# Radio_WMCU.net
KiCad netlist of a schematic drawn in Altium Designer
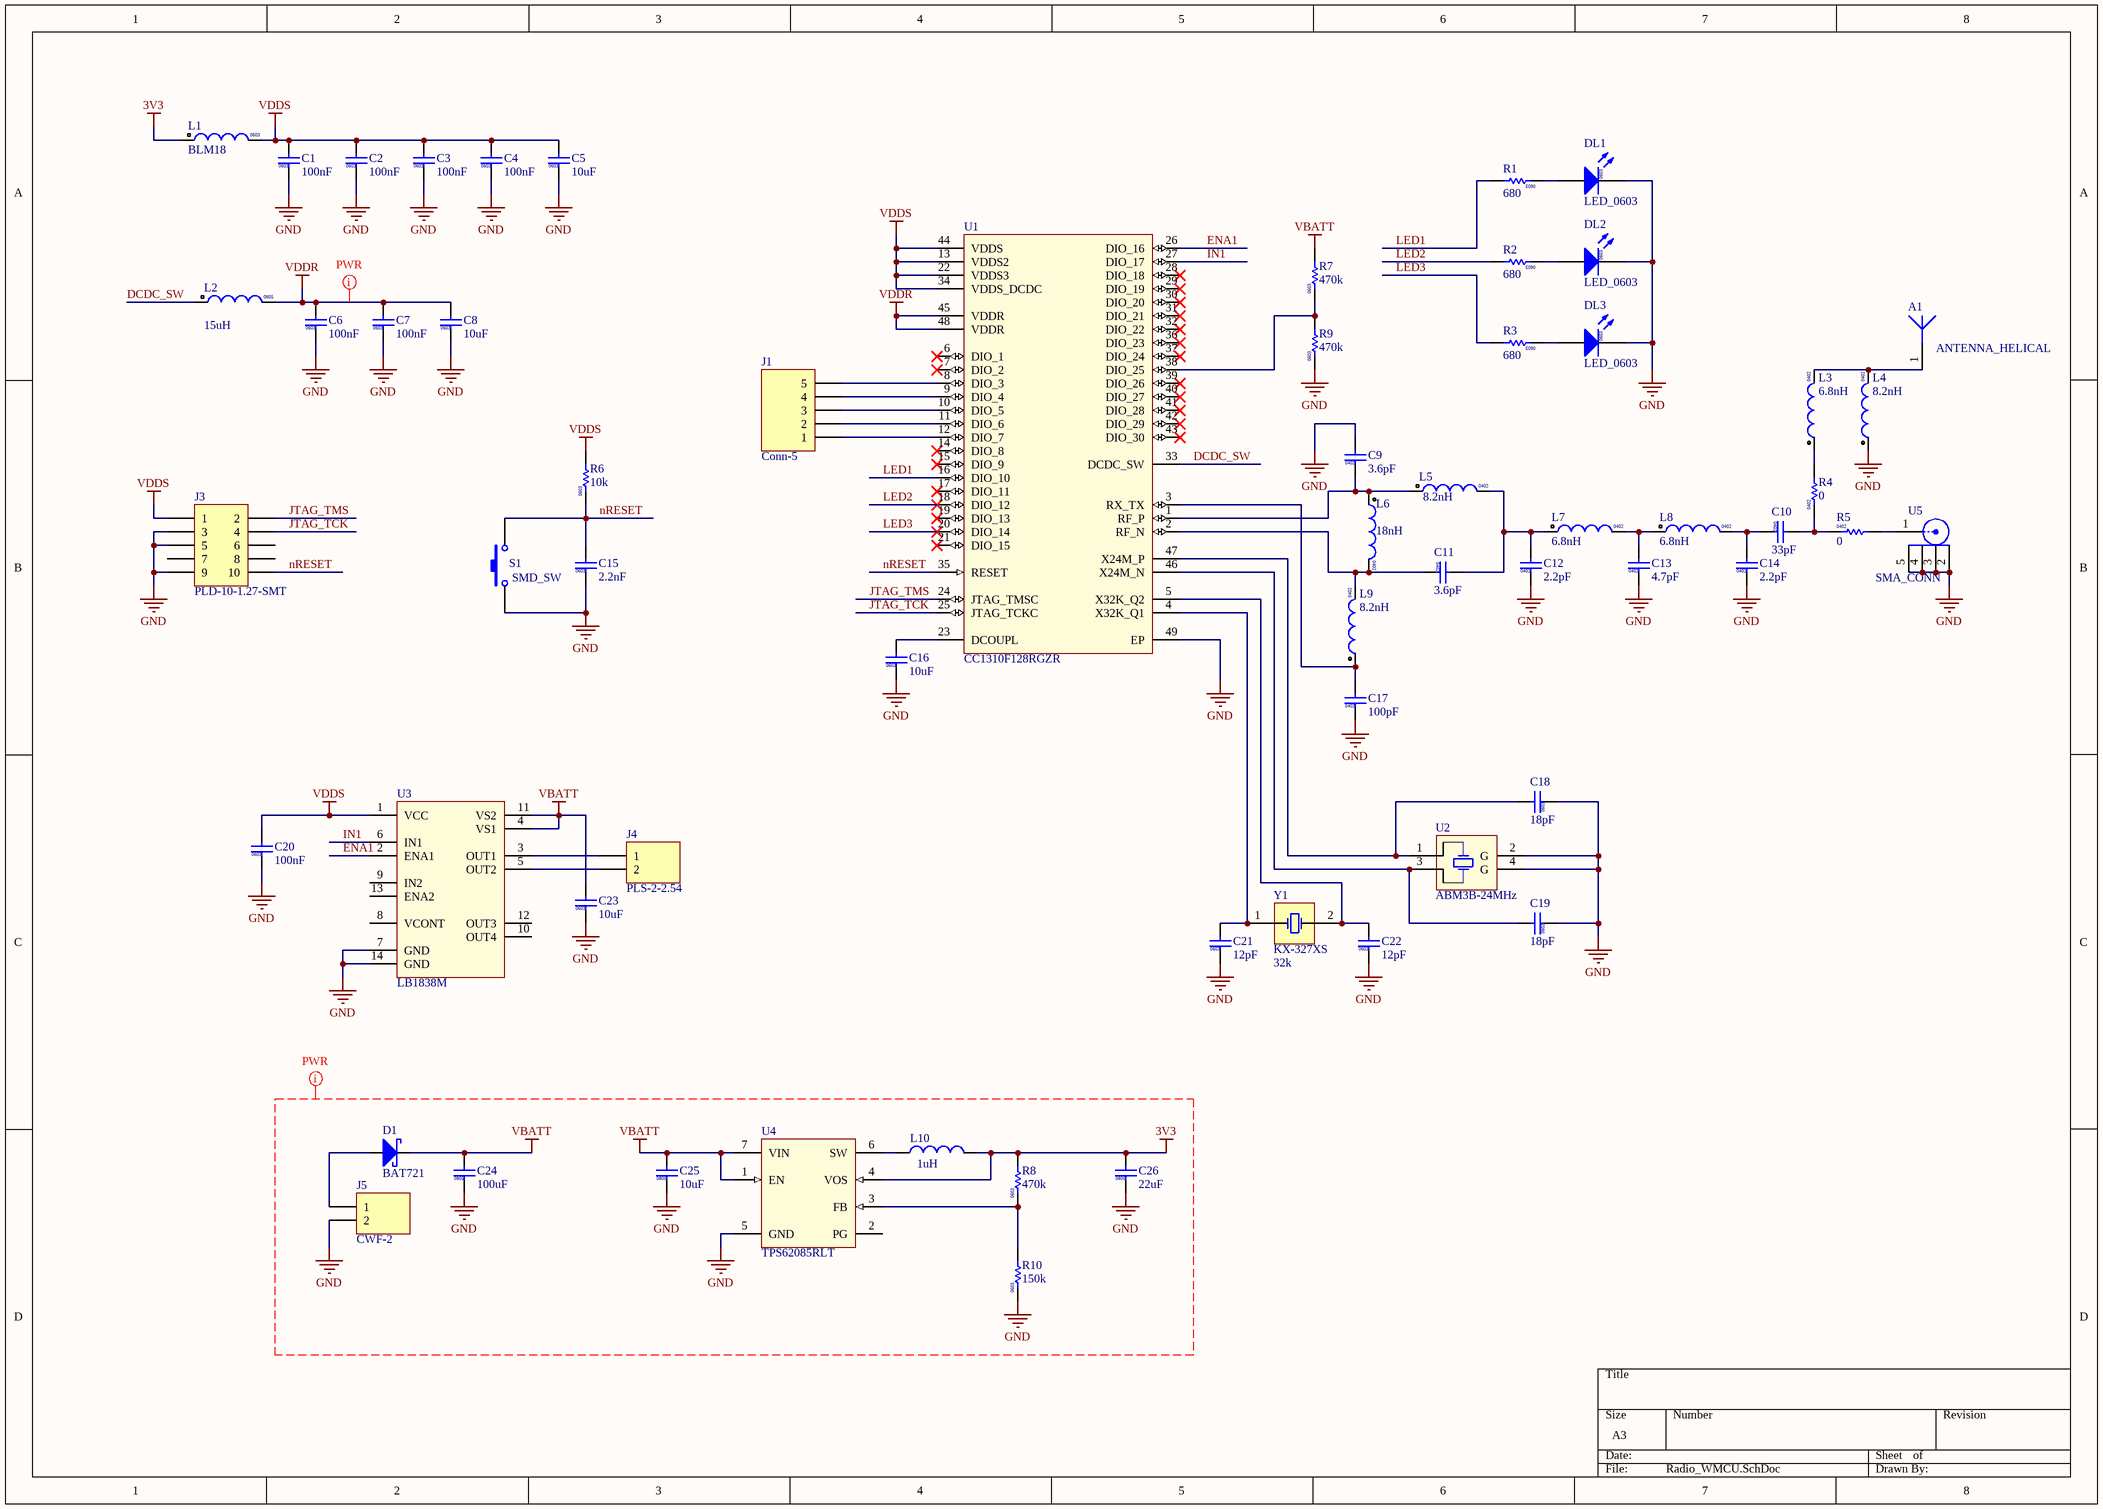
[diagram p0: Radio_WMCU.SchDoc]

(export (version "E")
  (design (tool "Eeschema 10.0.6"))
  (components
    (comp (ref "A1")
      (value "ANTENNA_HELICAL")
      (footprint "ANTENNA")
      (description "PCB helical antenna")
      (libsource (lib "Discrete") (part "ANTENNA_HELICAL"))
    )
    (comp (ref "C1")
      (value "100nF")
      (footprint "CAPC1608-0603M")
      (description "Capacitor 0603")
      (fields (field (name "Comment") "CAPC_0603"))
      (libsource (lib "Passive") (part "CAPC_0603"))
    )
    (comp (ref "C2")
      (value "100nF")
      (footprint "CAPC1608-0603M")
      (description "Capacitor 0603")
      (fields (field (name "Comment") "CAPC_0603"))
      (libsource (lib "Passive") (part "CAPC_0603"))
    )
    (comp (ref "C3")
      (value "100nF")
      (footprint "CAPC1608-0603M")
      (description "Capacitor 0603")
      (fields (field (name "Comment") "CAPC_0603"))
      (libsource (lib "Passive") (part "CAPC_0603"))
    )
    (comp (ref "C4")
      (value "100nF")
      (footprint "CAPC1608-0603M")
      (description "Capacitor 0603")
      (fields (field (name "Comment") "CAPC_0603"))
      (libsource (lib "Passive") (part "CAPC_0603"))
    )
    (comp (ref "C5")
      (value "10uF")
      (footprint "CAPC1608-0603M")
      (description "Capacitor 0603")
      (fields (field (name "Comment") "CAPC_0603"))
      (libsource (lib "Passive") (part "CAPC_0603"))
    )
    (comp (ref "C6")
      (value "100nF")
      (footprint "CAPC1608-0603M")
      (description "Capacitor 0603")
      (fields (field (name "Comment") "CAPC_0603"))
      (libsource (lib "Passive") (part "CAPC_0603"))
    )
    (comp (ref "C7")
      (value "100nF")
      (footprint "CAPC1608-0603M")
      (description "Capacitor 0603")
      (fields (field (name "Comment") "CAPC_0603"))
      (libsource (lib "Passive") (part "CAPC_0603"))
    )
    (comp (ref "C8")
      (value "10uF")
      (footprint "CAPC1608-0603M")
      (description "Capacitor 0603")
      (fields (field (name "Comment") "CAPC_0603"))
      (libsource (lib "Passive") (part "CAPC_0603"))
    )
    (comp (ref "C9")
      (value "3.6pF")
      (footprint "CAPC1005-0402M")
      (description "Capacitor 0402")
      (fields (field (name "Comment") "CAPC_0402"))
      (libsource (lib "Passive") (part "CAPC_0402"))
    )
    (comp (ref "C10")
      (value "33pF")
      (footprint "CAPC1005-0402M")
      (description "Capacitor 0402")
      (fields (field (name "Comment") "CAPC_0402"))
      (libsource (lib "Passive") (part "CAPC_0402"))
    )
    (comp (ref "C11")
      (value "3.6pF")
      (footprint "CAPC1005-0402M")
      (description "Capacitor 0402")
      (fields (field (name "Comment") "CAPC_0402"))
      (libsource (lib "Passive") (part "CAPC_0402"))
    )
    (comp (ref "C12")
      (value "2.2pF")
      (footprint "CAPC1005-0402M")
      (description "Capacitor 0402")
      (fields (field (name "Comment") "CAPC_0402"))
      (libsource (lib "Passive") (part "CAPC_0402"))
    )
    (comp (ref "C13")
      (value "4.7pF")
      (footprint "CAPC1005-0402M")
      (description "Capacitor 0402")
      (fields (field (name "Comment") "CAPC_0402"))
      (libsource (lib "Passive") (part "CAPC_0402"))
    )
    (comp (ref "C14")
      (value "2.2pF")
      (footprint "CAPC1005-0402M")
      (description "Capacitor 0402")
      (fields (field (name "Comment") "CAPC_0402"))
      (libsource (lib "Passive") (part "CAPC_0402"))
    )
    (comp (ref "C15")
      (value "2.2nF")
      (footprint "CAPC1608-0603M")
      (description "Capacitor 0603")
      (fields (field (name "Comment") "CAPC_0603"))
      (libsource (lib "Passive") (part "CAPC_0603"))
    )
    (comp (ref "C16")
      (value "10uF")
      (footprint "CAPC1608-0603M")
      (description "Capacitor 0603")
      (fields (field (name "Comment") "CAPC_0603"))
      (libsource (lib "Passive") (part "CAPC_0603"))
    )
    (comp (ref "C17")
      (value "100pF")
      (footprint "CAPC1005-0402M")
      (description "Capacitor 0402")
      (fields (field (name "Comment") "CAPC_0402"))
      (libsource (lib "Passive") (part "CAPC_0402"))
    )
    (comp (ref "C18")
      (value "18pF")
      (footprint "CAPC1608-0603M")
      (description "Capacitor 0603")
      (fields (field (name "Comment") "CAPC_0603"))
      (libsource (lib "Passive") (part "CAPC_0603"))
    )
    (comp (ref "C19")
      (value "18pF")
      (footprint "CAPC1608-0603M")
      (description "Capacitor 0603")
      (fields (field (name "Comment") "CAPC_0603"))
      (libsource (lib "Passive") (part "CAPC_0603"))
    )
    (comp (ref "C20")
      (value "100nF")
      (footprint "CAPC1608-0603M")
      (description "Capacitor 0603")
      (fields (field (name "Comment") "CAPC_0603"))
      (libsource (lib "Passive") (part "CAPC_0603"))
    )
    (comp (ref "C21")
      (value "12pF")
      (footprint "CAPC1608-0603M")
      (description "Capacitor 0603")
      (fields (field (name "Comment") "CAPC_0603"))
      (libsource (lib "Passive") (part "CAPC_0603"))
    )
    (comp (ref "C22")
      (value "12pF")
      (footprint "CAPC1608-0603M")
      (description "Capacitor 0603")
      (fields (field (name "Comment") "CAPC_0603"))
      (libsource (lib "Passive") (part "CAPC_0603"))
    )
    (comp (ref "C23")
      (value "10uF")
      (footprint "CAPC1608-0603M")
      (description "Capacitor 0603")
      (fields (field (name "Comment") "CAPC_0603"))
      (libsource (lib "Passive") (part "CAPC_0603"))
    )
    (comp (ref "C24")
      (value "100uF")
      (footprint "CAPC2012-0805M")
      (description "Capacitor 0805")
      (fields (field (name "Comment") "CAPC_0805"))
      (libsource (lib "Passive") (part "CAPC_0805"))
    )
    (comp (ref "C25")
      (value "10uF")
      (footprint "CAPC2012-0805M")
      (description "Capacitor 0805")
      (fields (field (name "Comment") "CAPC_0805"))
      (libsource (lib "Passive") (part "CAPC_0805"))
    )
    (comp (ref "C26")
      (value "22uF")
      (footprint "CAPC2012-0805M")
      (description "Capacitor 0805")
      (fields (field (name "Comment") "CAPC_0805"))
      (libsource (lib "Passive") (part "CAPC_0805"))
    )
    (comp (ref "D1")
      (value "BAT721")
      (footprint "SOT23-3M")
      (description "BAT721 Schottky diode(s)")
      (libsource (lib "Discrete") (part "BAT721"))
    )
    (comp (ref "DL1")
      (value "LED_0603")
      (footprint "DIODEC1608-0603")
      (description "LED 0603")
      (fields (field (name "PART NUMBER") "*BL-..."))
      (libsource (lib "Discrete") (part "LED_0603"))
    )
    (comp (ref "DL2")
      (value "LED_0603")
      (footprint "DIODEC1608-0603")
      (description "LED 0603")
      (fields (field (name "PART NUMBER") "*BL-..."))
      (libsource (lib "Discrete") (part "LED_0603"))
    )
    (comp (ref "DL3")
      (value "LED_0603")
      (footprint "DIODEC1608-0603")
      (description "LED 0603")
      (fields (field (name "PART NUMBER") "*BL-..."))
      (libsource (lib "Discrete") (part "LED_0603"))
    )
    (comp (ref "J1")
      (value "Conn-5")
      (footprint "CONN-5-2.54")
      (description "Header, 6-Pin, Dual row")
      (fields (field (name "PUBLISHER") "Altium Limited"))
      (libsource (lib "Connectors_dif") (part "Conn-5"))
    )
    (comp (ref "J3")
      (value "PLD-10-1.27-SMT")
      (footprint "PLD-10-1.27-SMT")
      (fields (field (name "PUBLISHER") "Altium Limited"))
      (libsource (lib "Connectors_dif") (part "PLD-10-1.27-SMT"))
    )
    (comp (ref "J4")
      (value "PLS-2-2.54")
      (footprint "PLS-2-2.54")
      (fields (field (name "PUBLISHER") "Altium Limited"))
      (libsource (lib "Connectors_dif") (part "PLS-2-2.54"))
    )
    (comp (ref "J5") (value "CWF-2") (footprint "CWF-2") (libsource (lib "Connectors_dif") (part "CWF-2")))
    (comp (ref "L1")
      (value "BLM18")
      (footprint "INDC1608M")
      (description "Chip Inductor, Body Body 1.6x0.8mm")
      (fields (field (name "Comment") "INDC-0603"))
      (libsource (lib "Passive") (part "INDC-0603"))
    )
    (comp (ref "L2")
      (value "15uH")
      (footprint "INDC2012M")
      (description "Chip Inductor, Body Body 2.0x1.2mm")
      (fields (field (name "Comment") "INDC-0805"))
      (libsource (lib "Passive") (part "INDC-0805"))
    )
    (comp (ref "L3")
      (value "6.8nH")
      (footprint "INDC1005-0402-RF2.4GHz")
      (description "Chip Inductor, Body 1.0x0.5mm")
      (fields (field (name "Comment") "INDC-0402") (field (name "PUBLISHER") "Altium Limited"))
      (libsource (lib "Passive") (part "INDC-0402"))
    )
    (comp (ref "L4")
      (value "8.2nH")
      (footprint "INDC1005-0402-RF2.4GHz")
      (description "Chip Inductor, Body 1.0x0.5mm")
      (fields (field (name "Comment") "INDC-0402") (field (name "PUBLISHER") "Altium Limited"))
      (libsource (lib "Passive") (part "INDC-0402"))
    )
    (comp (ref "L5")
      (value "8.2nH")
      (footprint "INDC1005-0402-RF2.4GHz")
      (description "Chip Inductor, Body 1.0x0.5mm")
      (fields (field (name "Comment") "INDC-0402") (field (name "PUBLISHER") "Altium Limited"))
      (libsource (lib "") (part "INDC-0402_1"))
    )
    (comp (ref "L6")
      (value "18nH")
      (footprint "INDC1005-0402-RF2.4GHz")
      (description "Chip Inductor, Body 1.0x0.5mm")
      (fields (field (name "Comment") "INDC-0402") (field (name "PUBLISHER") "Altium Limited"))
      (libsource (lib "Passive") (part "INDC-0402"))
    )
    (comp (ref "L7")
      (value "6.8nH")
      (footprint "INDC1005-0402-RF2.4GHz")
      (description "Chip Inductor, Body 1.0x0.5mm")
      (fields (field (name "Comment") "INDC-0402") (field (name "PUBLISHER") "Altium Limited"))
      (libsource (lib "Passive") (part "INDC-0402"))
    )
    (comp (ref "L8")
      (value "6.8nH")
      (footprint "INDC1005-0402-RF2.4GHz")
      (description "Chip Inductor, Body 1.0x0.5mm")
      (fields (field (name "Comment") "INDC-0402") (field (name "PUBLISHER") "Altium Limited"))
      (libsource (lib "Passive") (part "INDC-0402"))
    )
    (comp (ref "L9")
      (value "8.2nH")
      (footprint "INDC1005-0402-RF2.4GHz")
      (description "Chip Inductor, Body 1.0x0.5mm")
      (fields (field (name "Comment") "INDC-0402") (field (name "PUBLISHER") "Altium Limited"))
      (libsource (lib "Passive") (part "INDC-0402"))
    )
    (comp (ref "L10")
      (value "1uH")
      (footprint "XFL4015")
      (description "Power Inductors")
      (fields (field (name "Comment") "XFL4015"))
      (libsource (lib "Passive") (part "XFL4015"))
    )
    (comp (ref "R1")
      (value "680")
      (footprint "RESC1608-0603M")
      (description "Resistor 0603")
      (fields (field (name "Comment") "RESC_0603"))
      (libsource (lib "Passive") (part "RESC_0603"))
    )
    (comp (ref "R2")
      (value "680")
      (footprint "RESC1608-0603M")
      (description "Resistor 0603")
      (fields (field (name "Comment") "RESC_0603"))
      (libsource (lib "Passive") (part "RESC_0603"))
    )
    (comp (ref "R3")
      (value "680")
      (footprint "RESC1608-0603M")
      (description "Resistor 0603")
      (fields (field (name "Comment") "RESC_0603"))
      (libsource (lib "Passive") (part "RESC_0603"))
    )
    (comp (ref "R4")
      (value "0")
      (footprint "RESC1005-0402M")
      (description "Resistor 0402")
      (fields (field (name "Comment") "RESC_0402"))
      (libsource (lib "Passive") (part "RESC_0402"))
    )
    (comp (ref "R5")
      (value "0")
      (footprint "RESC1005-0402M")
      (description "Resistor 0402")
      (fields (field (name "Comment") "RESC_0402"))
      (libsource (lib "Passive") (part "RESC_0402"))
    )
    (comp (ref "R6")
      (value "10k")
      (footprint "RESC1608-0603M")
      (description "Resistor 0603")
      (fields (field (name "Comment") "RESC_0603"))
      (libsource (lib "Passive") (part "RESC_0603"))
    )
    (comp (ref "R7")
      (value "470k")
      (footprint "RESC1608-0603M")
      (description "Resistor 0603")
      (fields (field (name "Comment") "RESC_0603"))
      (libsource (lib "Passive") (part "RESC_0603"))
    )
    (comp (ref "R8")
      (value "470k")
      (footprint "RESC1608-0603M")
      (description "Resistor 0603")
      (fields (field (name "Comment") "RESC_0603"))
      (libsource (lib "Passive") (part "RESC_0603"))
    )
    (comp (ref "R9")
      (value "470k")
      (footprint "RESC1608-0603M")
      (description "Resistor 0603")
      (fields (field (name "Comment") "RESC_0603"))
      (libsource (lib "Passive") (part "RESC_0603"))
    )
    (comp (ref "R10")
      (value "150k")
      (footprint "RESC1608-0603M")
      (description "Resistor 0603")
      (fields (field (name "Comment") "RESC_0603"))
      (libsource (lib "Passive") (part "RESC_0603"))
    )
    (comp (ref "S1")
      (value "SMD_SW")
      (footprint "SMD_SW_1")
      (description "Switch")
      (fields (field (name "PUBLISHER") "Altium Limited"))
      (libsource (lib "General_Proj") (part "SMD_SW"))
    )
    (comp (ref "U1")
      (value "CC1310F128RGZR")
      (footprint "QFN-48M")
      (description "Ultralow Power Sub-1-GHz Wireless MCU")
      (libsource (lib "Analog_IC") (part "CC1310F128RGZR"))
    )
    (comp (ref "U2")
      (value "ABM3B-24MHz")
      (footprint "ABM3B-24MHz")
      (description "Crystal Oscillator, 24 MHz, SMD, 5mm x 3.2mm")
      (libsource (lib "Passive") (part "ABM3B-24MHz"))
    )
    (comp (ref "U3")
      (value "LB1838M")
      (footprint "MFP14S_M")
      (description "Low-Voltage, Bidiractional Motor Driver")
      (libsource (lib "Analog_IC") (part "LB1838M"))
    )
    (comp (ref "U4")
      (value "TPS62085RLT")
      (footprint "RLT7-0506")
      (description "Step-Down Converter With Hiccup Short-Circuit Protection, 2.5-V to 6.0-V input Voltage Range")
      (libsource (lib "Analog_IC") (part "TPS62085RLT"))
    )
    (comp (ref "U5")
      (value "SMA_CONN")
      (footprint "SMA_CONN")
      (description "SMA Straight PCB Socket")
      (libsource (lib "RCMG") (part "SMA_CONN"))
    )
    (comp (ref "Y1")
      (value "KX-327XS")
      (footprint "KX-327xs")
      (description "Surface Mount Quartz Crystal")
      (fields (field (name "ALTIUM_VALUE") "32k"))
      (libsource (lib "Passive") (part "KX-327XS"))
    )
  )
  (nets
    (net (code "1") (name "/DCDC_SW") (class "Default")
      (node (ref "L2") (pin "1") (pinfunction "1_1") (pintype "passive"))
      (node (ref "U1") (pin "33") (pinfunction "DCDC_SW_33") (pintype "power_in"))
    )
    (net (code "2") (name "/ENA1") (class "Default")
      (node (ref "U1") (pin "26") (pinfunction "DIO_16_26") (pintype "bidirectional"))
      (node (ref "U3") (pin "2") (pinfunction "ENA1_2") (pintype "passive"))
    )
    (net (code "3") (name "/IN1") (class "Default")
      (node (ref "U1") (pin "27") (pinfunction "DIO_17_27") (pintype "bidirectional"))
      (node (ref "U3") (pin "6") (pinfunction "IN1_6") (pintype "passive"))
    )
    (net (code "4") (name "/JTAG_TCK") (class "Default")
      (node (ref "J3") (pin "4") (pinfunction "4_4") (pintype "passive"))
      (node (ref "U1") (pin "25") (pinfunction "JTAG_TCKC_25") (pintype "bidirectional"))
    )
    (net (code "5") (name "/JTAG_TMS") (class "Default")
      (node (ref "J3") (pin "2") (pinfunction "2_2") (pintype "passive"))
      (node (ref "U1") (pin "24") (pinfunction "JTAG_TMSC_24") (pintype "bidirectional"))
    )
    (net (code "6") (name "/LED1") (class "Default")
      (node (ref "R1") (pin "2") (pinfunction "2_2") (pintype "passive"))
      (node (ref "U1") (pin "16") (pinfunction "DIO_10_16") (pintype "bidirectional"))
    )
    (net (code "7") (name "/LED2") (class "Default")
      (node (ref "R2") (pin "2") (pinfunction "2_2") (pintype "passive"))
      (node (ref "U1") (pin "18") (pinfunction "DIO_12_18") (pintype "bidirectional"))
    )
    (net (code "8") (name "/LED3") (class "Default")
      (node (ref "R3") (pin "2") (pinfunction "2_2") (pintype "passive"))
      (node (ref "U1") (pin "20") (pinfunction "DIO_14_20") (pintype "bidirectional"))
    )
    (net (code "9") (name "/nRESET") (class "Default")
      (node (ref "C15") (pin "2") (pinfunction "2_2") (pintype "passive"))
      (node (ref "J3") (pin "10") (pinfunction "10_10") (pintype "passive"))
      (node (ref "R6") (pin "1") (pinfunction "1_1") (pintype "passive"))
      (node (ref "S1") (pin "2") (pinfunction "2_2") (pintype "passive"))
      (node (ref "U1") (pin "35") (pinfunction "RESET_35") (pintype "input"))
    )
    (net (code "10") (name "3V3") (class "Default")
      (node (ref "C26") (pin "2") (pinfunction "2_2") (pintype "passive"))
      (node (ref "L1") (pin "1") (pinfunction "1_1") (pintype "passive"))
      (node (ref "L10") (pin "2") (pinfunction "2_2") (pintype "passive"))
      (node (ref "R8") (pin "2") (pinfunction "2_2") (pintype "passive"))
      (node (ref "U4") (pin "4") (pinfunction "VOS_4") (pintype "input"))
    )
    (net (code "11") (name "GND") (class "Default")
      (node (ref "C1") (pin "1") (pinfunction "1_1") (pintype "passive"))
      (node (ref "C12") (pin "1") (pinfunction "1_1") (pintype "passive"))
      (node (ref "C13") (pin "1") (pinfunction "1_1") (pintype "passive"))
      (node (ref "C14") (pin "1") (pinfunction "1_1") (pintype "passive"))
      (node (ref "C15") (pin "1") (pinfunction "1_1") (pintype "passive"))
      (node (ref "C16") (pin "1") (pinfunction "1_1") (pintype "passive"))
      (node (ref "C17") (pin "1") (pinfunction "1_1") (pintype "passive"))
      (node (ref "C18") (pin "1") (pinfunction "1_1") (pintype "passive"))
      (node (ref "C19") (pin "1") (pinfunction "1_1") (pintype "passive"))
      (node (ref "C2") (pin "1") (pinfunction "1_1") (pintype "passive"))
      (node (ref "C20") (pin "1") (pinfunction "1_1") (pintype "passive"))
      (node (ref "C21") (pin "1") (pinfunction "1_1") (pintype "passive"))
      (node (ref "C22") (pin "1") (pinfunction "1_1") (pintype "passive"))
      (node (ref "C23") (pin "1") (pinfunction "1_1") (pintype "passive"))
      (node (ref "C24") (pin "1") (pinfunction "1_1") (pintype "passive"))
      (node (ref "C25") (pin "1") (pinfunction "1_1") (pintype "passive"))
      (node (ref "C26") (pin "1") (pinfunction "1_1") (pintype "passive"))
      (node (ref "C3") (pin "1") (pinfunction "1_1") (pintype "passive"))
      (node (ref "C4") (pin "1") (pinfunction "1_1") (pintype "passive"))
      (node (ref "C5") (pin "1") (pinfunction "1_1") (pintype "passive"))
      (node (ref "C6") (pin "1") (pinfunction "1_1") (pintype "passive"))
      (node (ref "C7") (pin "1") (pinfunction "1_1") (pintype "passive"))
      (node (ref "C8") (pin "1") (pinfunction "1_1") (pintype "passive"))
      (node (ref "C9") (pin "2") (pinfunction "2_2") (pintype "passive"))
      (node (ref "DL1") (pin "2") (pinfunction "K_2") (pintype "passive"))
      (node (ref "DL2") (pin "2") (pinfunction "K_2") (pintype "passive"))
      (node (ref "DL3") (pin "2") (pinfunction "K_2") (pintype "passive"))
      (node (ref "J3") (pin "3") (pinfunction "3_3") (pintype "passive"))
      (node (ref "J3") (pin "5") (pinfunction "5_5") (pintype "passive"))
      (node (ref "J3") (pin "9") (pinfunction "9_9") (pintype "passive"))
      (node (ref "J5") (pin "2") (pinfunction "2_2") (pintype "passive"))
      (node (ref "L4") (pin "1") (pinfunction "1_1") (pintype "passive"))
      (node (ref "R10") (pin "1") (pinfunction "1_1") (pintype "passive"))
      (node (ref "R9") (pin "1") (pinfunction "1_1") (pintype "passive"))
      (node (ref "S1") (pin "1") (pinfunction "1_1") (pintype "passive"))
      (node (ref "U1") (pin "49") (pinfunction "EP_49") (pintype "power_in"))
      (node (ref "U2") (pin "2") (pinfunction "G_2") (pintype "power_in"))
      (node (ref "U2") (pin "4") (pinfunction "G_4") (pintype "power_in"))
      (node (ref "U3") (pin "14") (pinfunction "GND_14") (pintype "power_in"))
      (node (ref "U3") (pin "7") (pinfunction "GND_7") (pintype "power_in"))
      (node (ref "U4") (pin "5") (pinfunction "GND_5") (pintype "power_in"))
      (node (ref "U5") (pin "2") (pinfunction "2_2") (pintype "passive"))
      (node (ref "U5") (pin "3") (pinfunction "3_3") (pintype "passive"))
      (node (ref "U5") (pin "4") (pinfunction "4_4") (pintype "passive"))
      (node (ref "U5") (pin "5") (pinfunction "5_5") (pintype "passive"))
    )
    (net (code "12") (name "Net-(A1-Pad1)") (class "Default")
      (node (ref "A1") (pin "1") (pinfunction "1_1") (pintype "passive"))
      (node (ref "L3") (pin "2") (pinfunction "2_2") (pintype "passive"))
      (node (ref "L4") (pin "2") (pinfunction "2_2") (pintype "passive"))
    )
    (net (code "13") (name "Net-(C10-Pad1)") (class "Default")
      (node (ref "C10") (pin "1") (pinfunction "1_1") (pintype "passive"))
      (node (ref "C14") (pin "2") (pinfunction "2_2") (pintype "passive"))
      (node (ref "L8") (pin "2") (pinfunction "2_2") (pintype "passive"))
    )
    (net (code "14") (name "Net-(C10-Pad2)") (class "Default")
      (node (ref "C10") (pin "2") (pinfunction "2_2") (pintype "passive"))
      (node (ref "R4") (pin "1") (pinfunction "1_1") (pintype "passive"))
      (node (ref "R5") (pin "1") (pinfunction "1_1") (pintype "passive"))
    )
    (net (code "15") (name "Net-(C11-Pad2)") (class "Default")
      (node (ref "C11") (pin "2") (pinfunction "2_2") (pintype "passive"))
      (node (ref "C12") (pin "2") (pinfunction "2_2") (pintype "passive"))
      (node (ref "L5") (pin "2") (pinfunction "2_2") (pintype "passive"))
      (node (ref "L7") (pin "1") (pinfunction "1_1") (pintype "passive"))
    )
    (net (code "16") (name "Net-(C13-Pad2)") (class "Default")
      (node (ref "C13") (pin "2") (pinfunction "2_2") (pintype "passive"))
      (node (ref "L7") (pin "2") (pinfunction "2_2") (pintype "passive"))
      (node (ref "L8") (pin "1") (pinfunction "1_1") (pintype "passive"))
    )
    (net (code "17") (name "Net-(D1-A)") (class "Default")
      (node (ref "D1") (pin "1") (pinfunction "A_1") (pintype "passive"))
      (node (ref "J5") (pin "1") (pinfunction "1_1") (pintype "passive"))
    )
    (net (code "18") (name "Net-(DL1-A)") (class "Default")
      (node (ref "DL1") (pin "1") (pinfunction "A_1") (pintype "passive"))
      (node (ref "R1") (pin "1") (pinfunction "1_1") (pintype "passive"))
    )
    (net (code "19") (name "Net-(DL2-A)") (class "Default")
      (node (ref "DL2") (pin "1") (pinfunction "A_1") (pintype "passive"))
      (node (ref "R2") (pin "1") (pinfunction "1_1") (pintype "passive"))
    )
    (net (code "20") (name "Net-(DL3-A)") (class "Default")
      (node (ref "DL3") (pin "1") (pinfunction "A_1") (pintype "passive"))
      (node (ref "R3") (pin "1") (pinfunction "1_1") (pintype "passive"))
    )
    (net (code "21") (name "Net-(L3-Pad1)") (class "Default")
      (node (ref "L3") (pin "1") (pinfunction "1_1") (pintype "passive"))
      (node (ref "R4") (pin "2") (pinfunction "2_2") (pintype "passive"))
    )
    (net (code "22") (name "Net-(R5-Pad2)") (class "Default")
      (node (ref "R5") (pin "2") (pinfunction "2_2") (pintype "passive"))
      (node (ref "U5") (pin "1") (pinfunction "1_1") (pintype "passive"))
    )
    (net (code "23") (name "Net-(U1-DCOUPL)") (class "Default")
      (node (ref "C16") (pin "2") (pinfunction "2_2") (pintype "passive"))
      (node (ref "U1") (pin "23") (pinfunction "DCOUPL_23") (pintype "passive"))
    )
    (net (code "24") (name "Net-(U1-DIO_3)") (class "Default")
      (node (ref "J1") (pin "5") (pinfunction "5_5") (pintype "passive"))
      (node (ref "U1") (pin "8") (pinfunction "DIO_3_8") (pintype "bidirectional"))
    )
    (net (code "25") (name "Net-(U1-DIO_4)") (class "Default")
      (node (ref "J1") (pin "4") (pinfunction "4_4") (pintype "passive"))
      (node (ref "U1") (pin "9") (pinfunction "DIO_4_9") (pintype "bidirectional"))
    )
    (net (code "26") (name "Net-(U1-DIO_5)") (class "Default")
      (node (ref "J1") (pin "3") (pinfunction "3_3") (pintype "passive"))
      (node (ref "U1") (pin "10") (pinfunction "DIO_5_10") (pintype "bidirectional"))
    )
    (net (code "27") (name "Net-(U1-DIO_6)") (class "Default")
      (node (ref "J1") (pin "2") (pinfunction "2_2") (pintype "passive"))
      (node (ref "U1") (pin "11") (pinfunction "DIO_6_11") (pintype "bidirectional"))
    )
    (net (code "28") (name "Net-(U1-DIO_7)") (class "Default")
      (node (ref "J1") (pin "1") (pinfunction "1_1") (pintype "passive"))
      (node (ref "U1") (pin "12") (pinfunction "DIO_7_12") (pintype "bidirectional"))
    )
    (net (code "29") (name "Net-(U1-DIO_25)") (class "Default")
      (node (ref "R7") (pin "1") (pinfunction "1_1") (pintype "passive"))
      (node (ref "R9") (pin "2") (pinfunction "2_2") (pintype "passive"))
      (node (ref "U1") (pin "38") (pinfunction "DIO_25_38") (pintype "bidirectional"))
    )
    (net (code "30") (name "Net-(U1-RF_N)") (class "Default")
      (node (ref "C11") (pin "1") (pinfunction "1_1") (pintype "passive"))
      (node (ref "L6") (pin "2") (pinfunction "2_2") (pintype "passive"))
      (node (ref "L9") (pin "2") (pinfunction "2_2") (pintype "passive"))
      (node (ref "U1") (pin "2") (pinfunction "RF_N_2") (pintype "bidirectional"))
    )
    (net (code "31") (name "Net-(U1-RF_P)") (class "Default")
      (node (ref "C9") (pin "1") (pinfunction "1_1") (pintype "passive"))
      (node (ref "L5") (pin "1") (pinfunction "1_1") (pintype "passive"))
      (node (ref "L6") (pin "1") (pinfunction "1_1") (pintype "passive"))
      (node (ref "U1") (pin "1") (pinfunction "RF_P_1") (pintype "bidirectional"))
    )
    (net (code "32") (name "Net-(U1-RX_TX)") (class "Default")
      (node (ref "C17") (pin "2") (pinfunction "2_2") (pintype "passive"))
      (node (ref "L9") (pin "1") (pinfunction "1_1") (pintype "passive"))
      (node (ref "U1") (pin "3") (pinfunction "RX_TX_3") (pintype "bidirectional"))
    )
    (net (code "33") (name "Net-(U1-X24M_N)") (class "Default")
      (node (ref "C19") (pin "2") (pinfunction "2_2") (pintype "passive"))
      (node (ref "U1") (pin "46") (pinfunction "X24M_N_46") (pintype "passive"))
      (node (ref "U2") (pin "3") (pinfunction "3_3") (pintype "passive"))
    )
    (net (code "34") (name "Net-(U1-X24M_P)") (class "Default")
      (node (ref "C18") (pin "2") (pinfunction "2_2") (pintype "passive"))
      (node (ref "U1") (pin "47") (pinfunction "X24M_P_47") (pintype "passive"))
      (node (ref "U2") (pin "1") (pinfunction "1_1") (pintype "passive"))
    )
    (net (code "35") (name "Net-(U1-X32K_Q1)") (class "Default")
      (node (ref "C21") (pin "2") (pinfunction "2_2") (pintype "passive"))
      (node (ref "U1") (pin "4") (pinfunction "X32K_Q1_4") (pintype "passive"))
      (node (ref "Y1") (pin "1") (pintype "passive"))
    )
    (net (code "36") (name "Net-(U1-X32K_Q2)") (class "Default")
      (node (ref "C22") (pin "2") (pinfunction "2_2") (pintype "passive"))
      (node (ref "U1") (pin "5") (pinfunction "X32K_Q2_5") (pintype "passive"))
      (node (ref "Y1") (pin "2") (pintype "passive"))
    )
    (net (code "37") (name "Net-(U3-OUT1)") (class "Default")
      (node (ref "J4") (pin "1") (pinfunction "1_1") (pintype "passive"))
      (node (ref "U3") (pin "3") (pinfunction "OUT1_3") (pintype "passive"))
    )
    (net (code "38") (name "Net-(U3-OUT2)") (class "Default")
      (node (ref "J4") (pin "2") (pinfunction "2_2") (pintype "passive"))
      (node (ref "U3") (pin "5") (pinfunction "OUT2_5") (pintype "passive"))
    )
    (net (code "39") (name "Net-(U4-FB)") (class "Default")
      (node (ref "R10") (pin "2") (pinfunction "2_2") (pintype "passive"))
      (node (ref "R8") (pin "1") (pinfunction "1_1") (pintype "passive"))
      (node (ref "U4") (pin "3") (pinfunction "FB_3") (pintype "input"))
    )
    (net (code "40") (name "Net-(U4-SW)") (class "Default")
      (node (ref "L10") (pin "1") (pinfunction "1_1") (pintype "passive"))
      (node (ref "U4") (pin "6") (pinfunction "SW_6") (pintype "power_in"))
    )
    (net (code "41") (name "VBATT") (class "Default")
      (node (ref "C23") (pin "2") (pinfunction "2_2") (pintype "passive"))
      (node (ref "C24") (pin "2") (pinfunction "2_2") (pintype "passive"))
      (node (ref "C25") (pin "2") (pinfunction "2_2") (pintype "passive"))
      (node (ref "D1") (pin "3") (pinfunction "K_3") (pintype "passive"))
      (node (ref "R7") (pin "2") (pinfunction "2_2") (pintype "passive"))
      (node (ref "U3") (pin "11") (pinfunction "VS2_11") (pintype "power_in"))
      (node (ref "U3") (pin "4") (pinfunction "VS1_4") (pintype "power_in"))
      (node (ref "U4") (pin "1") (pinfunction "EN_1") (pintype "input"))
      (node (ref "U4") (pin "7") (pinfunction "VIN_7") (pintype "power_in"))
    )
    (net (code "42") (name "VDDR") (class "Default")
      (node (ref "C6") (pin "2") (pinfunction "2_2") (pintype "passive"))
      (node (ref "C7") (pin "2") (pinfunction "2_2") (pintype "passive"))
      (node (ref "C8") (pin "2") (pinfunction "2_2") (pintype "passive"))
      (node (ref "L2") (pin "2") (pinfunction "2_2") (pintype "passive"))
      (node (ref "U1") (pin "45") (pinfunction "VDDR_45") (pintype "power_in"))
      (node (ref "U1") (pin "48") (pinfunction "VDDR_48") (pintype "power_in"))
    )
    (net (code "43") (name "VDDS") (class "Default")
      (node (ref "C1") (pin "2") (pinfunction "2_2") (pintype "passive"))
      (node (ref "C2") (pin "2") (pinfunction "2_2") (pintype "passive"))
      (node (ref "C20") (pin "2") (pinfunction "2_2") (pintype "passive"))
      (node (ref "C3") (pin "2") (pinfunction "2_2") (pintype "passive"))
      (node (ref "C4") (pin "2") (pinfunction "2_2") (pintype "passive"))
      (node (ref "C5") (pin "2") (pinfunction "2_2") (pintype "passive"))
      (node (ref "J3") (pin "1") (pinfunction "1_1") (pintype "passive"))
      (node (ref "L1") (pin "2") (pinfunction "2_2") (pintype "passive"))
      (node (ref "R6") (pin "2") (pinfunction "2_2") (pintype "passive"))
      (node (ref "U1") (pin "13") (pinfunction "VDDS2_13") (pintype "power_in"))
      (node (ref "U1") (pin "22") (pinfunction "VDDS3_22") (pintype "power_in"))
      (node (ref "U1") (pin "34") (pinfunction "VDDS_DCDC_34") (pintype "power_in"))
      (node (ref "U1") (pin "44") (pinfunction "VDDS_44") (pintype "power_in"))
      (node (ref "U3") (pin "1") (pinfunction "VCC_1") (pintype "power_in"))
    )
    (net (code "44") (name "unconnected-(J3-Pad6)") (class "Default")
      (node (ref "J3") (pin "6") (pinfunction "6_6") (pintype "passive"))
    )
    (net (code "45") (name "unconnected-(J3-Pad7)") (class "Default")
      (node (ref "J3") (pin "7") (pinfunction "7_7") (pintype "passive"))
    )
    (net (code "46") (name "unconnected-(J3-Pad8)") (class "Default")
      (node (ref "J3") (pin "8") (pinfunction "8_8") (pintype "passive"))
    )
    (net (code "47") (name "unconnected-(U1-DIO_1-Pad6)") (class "Default")
      (node (ref "U1") (pin "6") (pinfunction "DIO_1_6") (pintype "bidirectional+no_connect"))
    )
    (net (code "48") (name "unconnected-(U1-DIO_2-Pad7)") (class "Default")
      (node (ref "U1") (pin "7") (pinfunction "DIO_2_7") (pintype "bidirectional+no_connect"))
    )
    (net (code "49") (name "unconnected-(U1-DIO_8-Pad14)") (class "Default")
      (node (ref "U1") (pin "14") (pinfunction "DIO_8_14") (pintype "bidirectional+no_connect"))
    )
    (net (code "50") (name "unconnected-(U1-DIO_9-Pad15)") (class "Default")
      (node (ref "U1") (pin "15") (pinfunction "DIO_9_15") (pintype "bidirectional+no_connect"))
    )
    (net (code "51") (name "unconnected-(U1-DIO_11-Pad17)") (class "Default")
      (node (ref "U1") (pin "17") (pinfunction "DIO_11_17") (pintype "bidirectional+no_connect"))
    )
    (net (code "52") (name "unconnected-(U1-DIO_13-Pad19)") (class "Default")
      (node (ref "U1") (pin "19") (pinfunction "DIO_13_19") (pintype "bidirectional+no_connect"))
    )
    (net (code "53") (name "unconnected-(U1-DIO_15-Pad21)") (class "Default")
      (node (ref "U1") (pin "21") (pinfunction "DIO_15_21") (pintype "bidirectional+no_connect"))
    )
    (net (code "54") (name "unconnected-(U1-DIO_18-Pad28)") (class "Default")
      (node (ref "U1") (pin "28") (pinfunction "DIO_18_28") (pintype "bidirectional+no_connect"))
    )
    (net (code "55") (name "unconnected-(U1-DIO_19-Pad29)") (class "Default")
      (node (ref "U1") (pin "29") (pinfunction "DIO_19_29") (pintype "bidirectional+no_connect"))
    )
    (net (code "56") (name "unconnected-(U1-DIO_20-Pad30)") (class "Default")
      (node (ref "U1") (pin "30") (pinfunction "DIO_20_30") (pintype "bidirectional+no_connect"))
    )
    (net (code "57") (name "unconnected-(U1-DIO_21-Pad31)") (class "Default")
      (node (ref "U1") (pin "31") (pinfunction "DIO_21_31") (pintype "bidirectional+no_connect"))
    )
    (net (code "58") (name "unconnected-(U1-DIO_22-Pad32)") (class "Default")
      (node (ref "U1") (pin "32") (pinfunction "DIO_22_32") (pintype "bidirectional+no_connect"))
    )
    (net (code "59") (name "unconnected-(U1-DIO_23-Pad36)") (class "Default")
      (node (ref "U1") (pin "36") (pinfunction "DIO_23_36") (pintype "bidirectional+no_connect"))
    )
    (net (code "60") (name "unconnected-(U1-DIO_24-Pad37)") (class "Default")
      (node (ref "U1") (pin "37") (pinfunction "DIO_24_37") (pintype "bidirectional+no_connect"))
    )
    (net (code "61") (name "unconnected-(U1-DIO_26-Pad39)") (class "Default")
      (node (ref "U1") (pin "39") (pinfunction "DIO_26_39") (pintype "bidirectional+no_connect"))
    )
    (net (code "62") (name "unconnected-(U1-DIO_27-Pad40)") (class "Default")
      (node (ref "U1") (pin "40") (pinfunction "DIO_27_40") (pintype "bidirectional+no_connect"))
    )
    (net (code "63") (name "unconnected-(U1-DIO_28-Pad41)") (class "Default")
      (node (ref "U1") (pin "41") (pinfunction "DIO_28_41") (pintype "bidirectional+no_connect"))
    )
    (net (code "64") (name "unconnected-(U1-DIO_29-Pad42)") (class "Default")
      (node (ref "U1") (pin "42") (pinfunction "DIO_29_42") (pintype "bidirectional+no_connect"))
    )
    (net (code "65") (name "unconnected-(U1-DIO_30-Pad43)") (class "Default")
      (node (ref "U1") (pin "43") (pinfunction "DIO_30_43") (pintype "bidirectional+no_connect"))
    )
    (net (code "66") (name "unconnected-(U3-ENA2-Pad13)") (class "Default")
      (node (ref "U3") (pin "13") (pinfunction "ENA2_13") (pintype "passive"))
    )
    (net (code "67") (name "unconnected-(U3-IN2-Pad9)") (class "Default")
      (node (ref "U3") (pin "9") (pinfunction "IN2_9") (pintype "passive"))
    )
    (net (code "68") (name "unconnected-(U3-OUT3-Pad12)") (class "Default")
      (node (ref "U3") (pin "12") (pinfunction "OUT3_12") (pintype "passive"))
    )
    (net (code "69") (name "unconnected-(U3-OUT4-Pad10)") (class "Default")
      (node (ref "U3") (pin "10") (pinfunction "OUT4_10") (pintype "passive"))
    )
    (net (code "70") (name "unconnected-(U3-VCONT-Pad8)") (class "Default")
      (node (ref "U3") (pin "8") (pinfunction "VCONT_8") (pintype "passive"))
    )
    (net (code "71") (name "unconnected-(U4-PG-Pad2)") (class "Default")
      (node (ref "U4") (pin "2") (pinfunction "PG_2") (pintype "passive"))
    )
  )
)
